# design.net
KiCad netlist of a schematic drawn in EasyEDA Pro
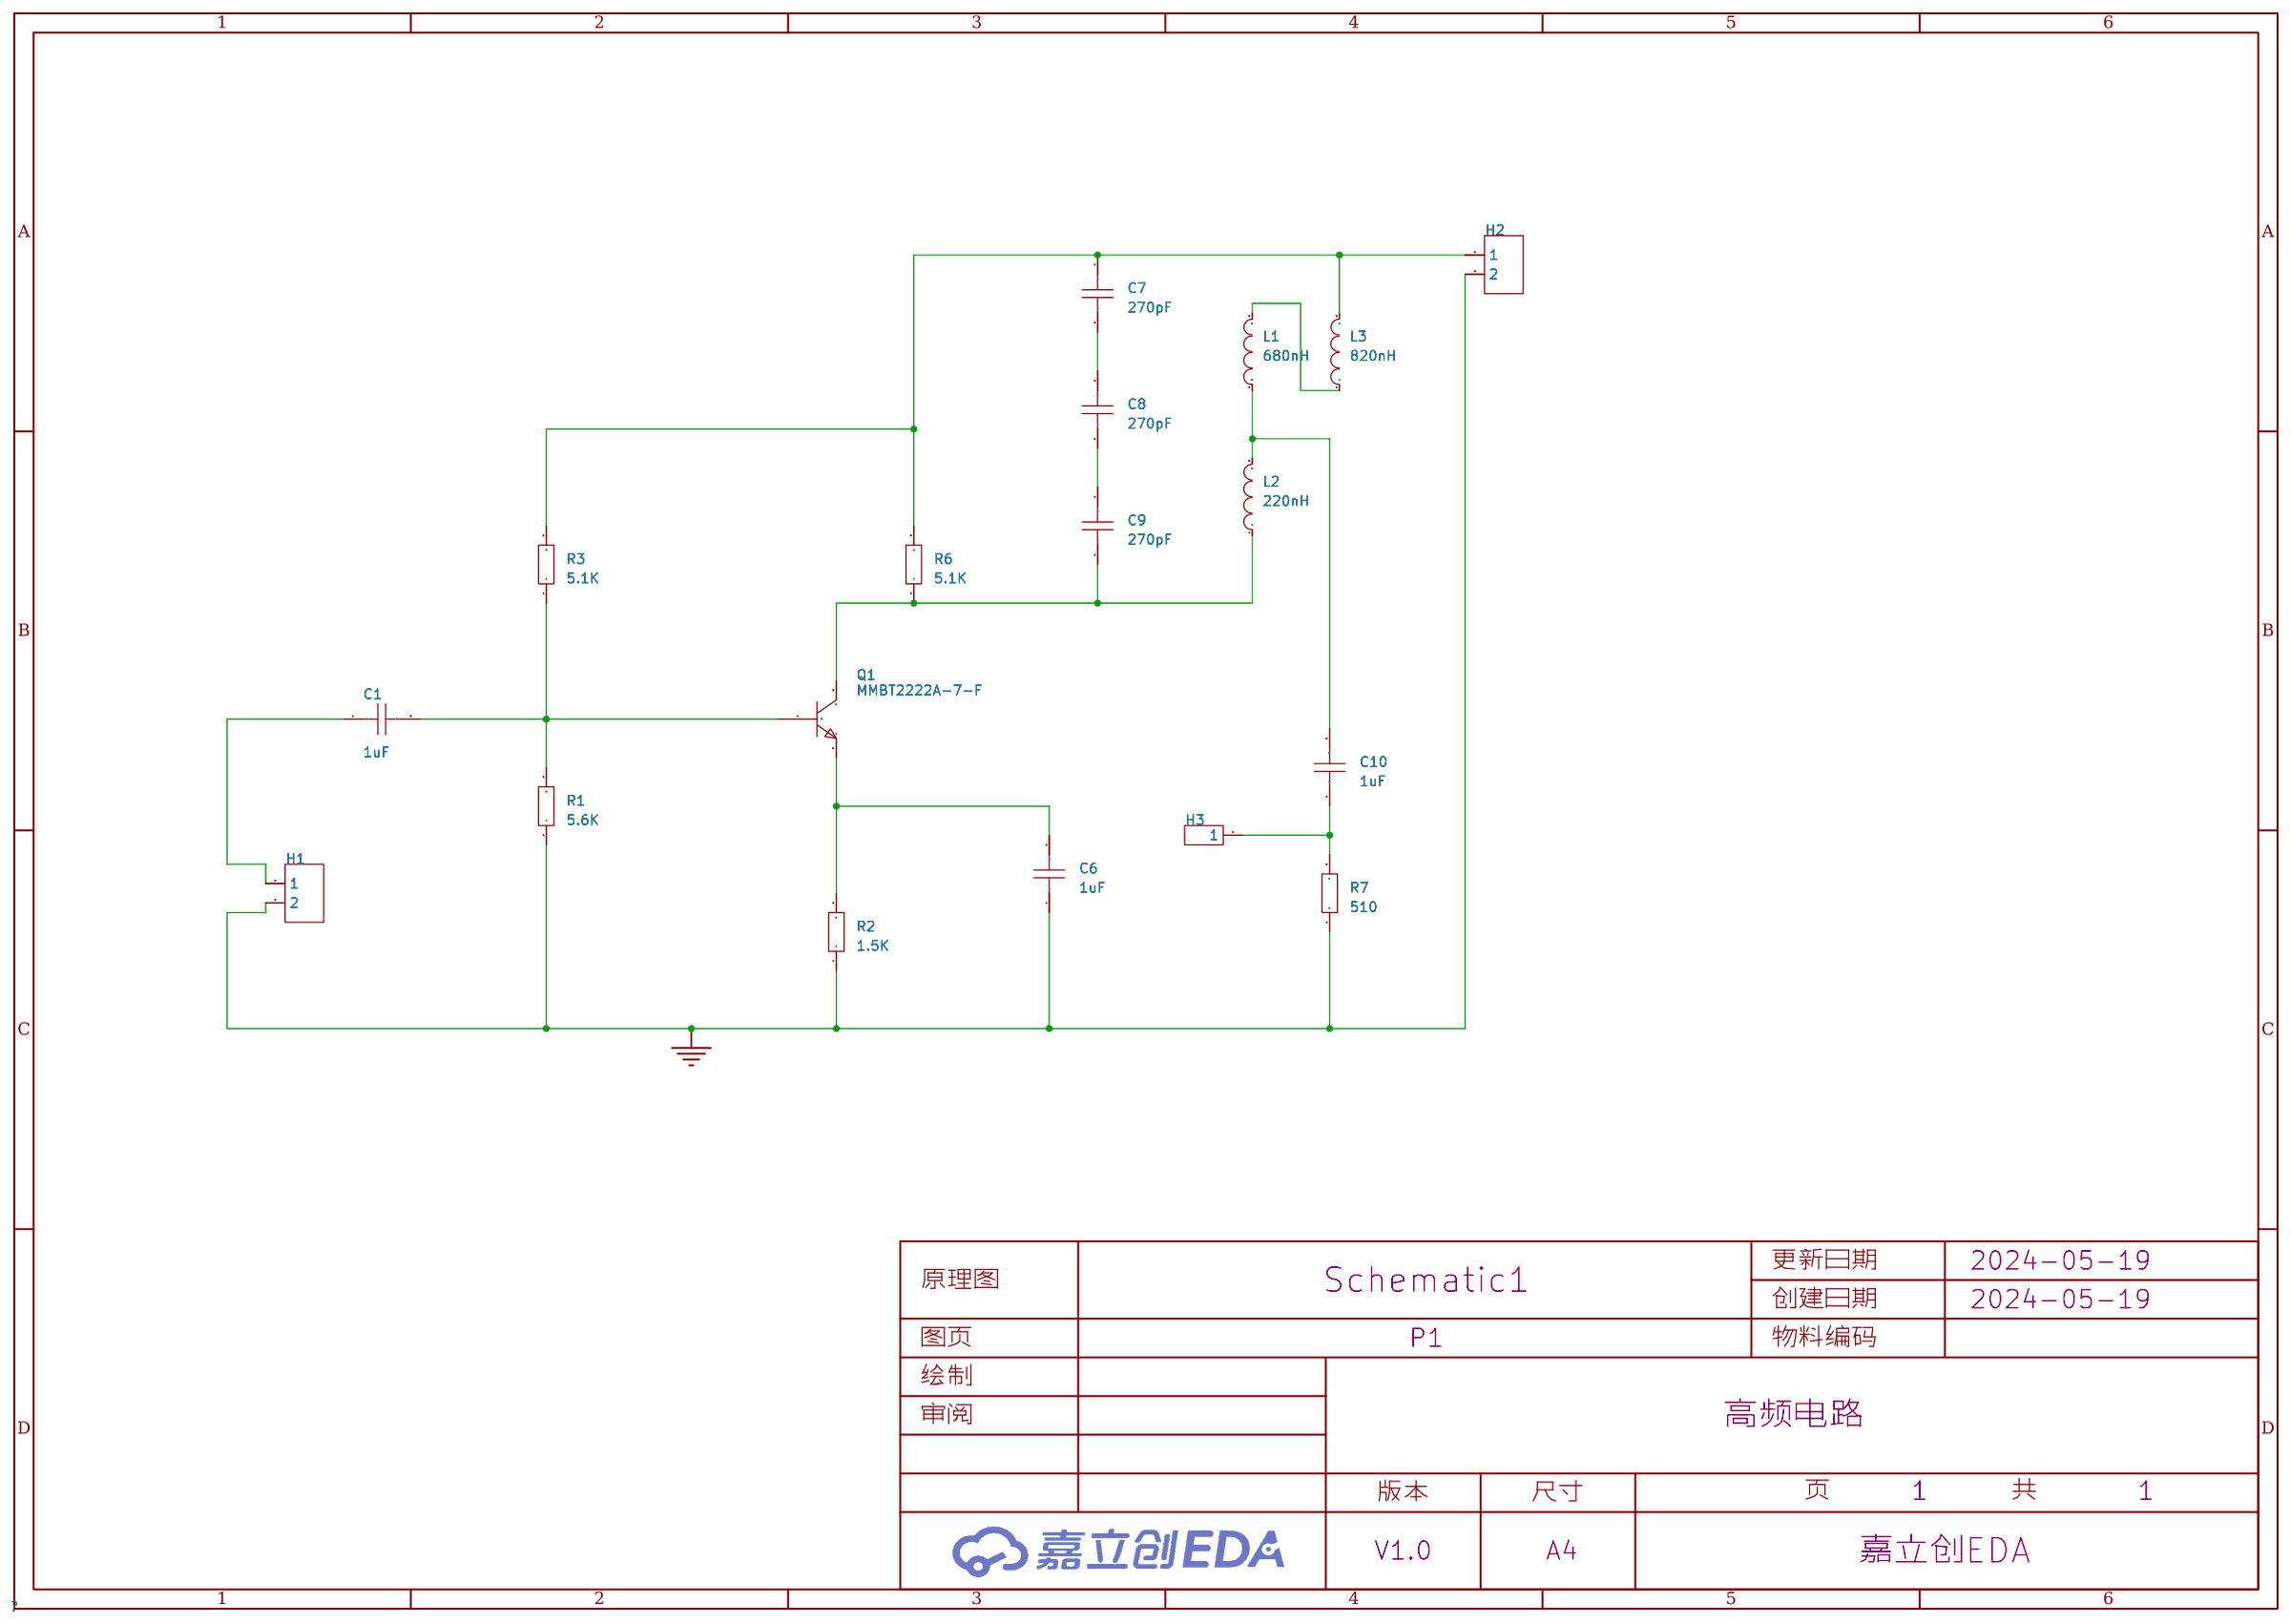
[diagram p0: schematic sheet]

(export (version "E")
  (design (tool "Eeschema 10.0.6"))
  (components
    (comp (ref "C1")
      (value "1uF")
      (footprint "easyedapro:C0805")
      (libsource (lib "easyedapro") (part "CapAcitance"))
    )
    (comp (ref "C6")
      (value "1uF")
      (footprint "easyedapro:C0805")
      (libsource (lib "easyedapro") (part "CapAcitance"))
    )
    (comp (ref "C7")
      (value "270pF")
      (footprint "easyedapro:C0805")
      (libsource (lib "easyedapro") (part "CapAcitance"))
    )
    (comp (ref "C8")
      (value "270pF")
      (footprint "easyedapro:C0805")
      (libsource (lib "easyedapro") (part "CapAcitance"))
    )
    (comp (ref "C9")
      (value "270pF")
      (footprint "easyedapro:C0805")
      (libsource (lib "easyedapro") (part "CapAcitance"))
    )
    (comp (ref "C10")
      (value "1uF")
      (footprint "easyedapro:C0805")
      (libsource (lib "easyedapro") (part "CapAcitance"))
    )
    (comp (ref "H1")
      (value "~")
      (footprint "easyedapro:HDR-TH_2P-P2.54-V-F")
      (libsource (lib "easyedapro") (part "Header-Female-2.54_1x2"))
    )
    (comp (ref "H2")
      (value "~")
      (footprint "easyedapro:HDR-TH_2P-P2.54-V-F")
      (libsource (lib "easyedapro") (part "Header-Female-2.54_1x2"))
    )
    (comp (ref "H3")
      (value "~")
      (footprint "easyedapro:HDR-TH_1P-V-M_XKB_X4611WV-01I-C28D40")
      (libsource (lib "easyedapro") (part "HDR_1x1"))
    )
    (comp (ref "L1")
      (value "680nH")
      (footprint "easyedapro:L0805")
      (libsource (lib "easyedapro") (part "SDFL2012S100KTF"))
    )
    (comp (ref "L2")
      (value "220nH")
      (footprint "easyedapro:L0805")
      (libsource (lib "easyedapro") (part "SDFL2012S100KTF"))
    )
    (comp (ref "L3")
      (value "820nH")
      (footprint "easyedapro:L0805")
      (libsource (lib "easyedapro") (part "SDFL2012S100KTF"))
    )
    (comp (ref "Q1")
      (value "MMBT2222A-7-F")
      (footprint "easyedapro:SOT-23-3_L2.9-W1.6-P1.90-LS2.8-BR")
      (description "晶体管类型:NPN;集电极电流(Ic):600mA;集射极击穿电压(Vceo):40V;功率(Pd):310mW;直流电流增益(hFE@Ic,Vce):100@150mA,10V;")
      (fields (field (name "Manufacturer") "DIODES(美台)"))
      (libsource (lib "easyedapro") (part "MMBT2222A-7-F"))
    )
    (comp (ref "R1") (value "5.6K") (footprint "easyedapro:R0603") (libsource (lib "easyedapro") (part "电阻")))
    (comp (ref "R2") (value "1.5K") (footprint "easyedapro:R0603") (libsource (lib "easyedapro") (part "电阻")))
    (comp (ref "R3") (value "5.1K") (footprint "easyedapro:R0603") (libsource (lib "easyedapro") (part "电阻")))
    (comp (ref "R6") (value "5.1K") (footprint "easyedapro:R0603") (libsource (lib "easyedapro") (part "电阻")))
    (comp (ref "R7") (value "510") (footprint "easyedapro:R0603") (libsource (lib "easyedapro") (part "电阻")))
  )
  (nets
    (net (code "1") (name "GND") (class "Default")
      (node (ref "C6") (pin "1") (pinfunction "1_1") (pintype "input"))
      (node (ref "H1") (pin "2") (pinfunction "2_2") (pintype "input"))
      (node (ref "H2") (pin "2") (pinfunction "2_2") (pintype "input"))
      (node (ref "R1") (pin "1") (pinfunction "1_1") (pintype "input"))
      (node (ref "R2") (pin "1") (pinfunction "1_1") (pintype "input"))
      (node (ref "R7") (pin "1") (pinfunction "1_1") (pintype "input"))
    )
    (net (code "2") (name "Net-(C1-Pad1)") (class "Default")
      (node (ref "C1") (pin "1") (pinfunction "1_1") (pintype "input"))
      (node (ref "H1") (pin "1") (pinfunction "1_1") (pintype "input"))
    )
    (net (code "3") (name "Net-(C7-Pad1)") (class "Default")
      (node (ref "C7") (pin "1") (pinfunction "1_1") (pintype "input"))
      (node (ref "H2") (pin "1") (pinfunction "1_1") (pintype "input"))
      (node (ref "L3") (pin "2") (pinfunction "2_2") (pintype "input"))
      (node (ref "R3") (pin "2") (pinfunction "2_2") (pintype "input"))
      (node (ref "R6") (pin "2") (pinfunction "2_2") (pintype "input"))
    )
    (net (code "4") (name "Net-(C7-Pad2)") (class "Default")
      (node (ref "C7") (pin "2") (pinfunction "2_2") (pintype "input"))
      (node (ref "C8") (pin "2") (pinfunction "2_2") (pintype "input"))
    )
    (net (code "5") (name "Net-(C8-Pad1)") (class "Default")
      (node (ref "C8") (pin "1") (pinfunction "1_1") (pintype "input"))
      (node (ref "C9") (pin "2") (pinfunction "2_2") (pintype "input"))
    )
    (net (code "6") (name "Net-(C10-Pad1)") (class "Default")
      (node (ref "C10") (pin "1") (pinfunction "1_1") (pintype "input"))
      (node (ref "H3") (pin "1") (pinfunction "1_1") (pintype "unspecified"))
      (node (ref "R7") (pin "2") (pinfunction "2_2") (pintype "input"))
    )
    (net (code "7") (name "Net-(C10-Pad2)") (class "Default")
      (node (ref "C10") (pin "2") (pinfunction "2_2") (pintype "input"))
      (node (ref "L1") (pin "1") (pinfunction "1_1") (pintype "input"))
      (node (ref "L2") (pin "2") (pinfunction "2_2") (pintype "input"))
    )
    (net (code "8") (name "Net-(L1-Pad2)") (class "Default")
      (node (ref "L1") (pin "2") (pinfunction "2_2") (pintype "input"))
      (node (ref "L3") (pin "1") (pinfunction "1_1") (pintype "input"))
    )
    (net (code "9") (name "Net-(Q1-B)") (class "Default")
      (node (ref "C1") (pin "2") (pinfunction "2_2") (pintype "input"))
      (node (ref "Q1") (pin "1") (pinfunction "B_1") (pintype "unspecified"))
      (node (ref "R1") (pin "2") (pinfunction "2_2") (pintype "input"))
      (node (ref "R3") (pin "1") (pinfunction "1_1") (pintype "input"))
    )
    (net (code "10") (name "Net-(Q1-C)") (class "Default")
      (node (ref "C9") (pin "1") (pinfunction "1_1") (pintype "input"))
      (node (ref "L2") (pin "1") (pinfunction "1_1") (pintype "input"))
      (node (ref "Q1") (pin "3") (pinfunction "C_3") (pintype "unspecified"))
      (node (ref "R6") (pin "1") (pinfunction "1_1") (pintype "input"))
    )
    (net (code "11") (name "Net-(Q1-E)") (class "Default")
      (node (ref "C6") (pin "2") (pinfunction "2_2") (pintype "input"))
      (node (ref "Q1") (pin "2") (pinfunction "E_2") (pintype "unspecified"))
      (node (ref "R2") (pin "2") (pinfunction "2_2") (pintype "input"))
    )
  )
)
